# ltc3783-boost-driver-test-mk-1_0_0.net
KiCad netlist of a schematic drawn in EAGLE
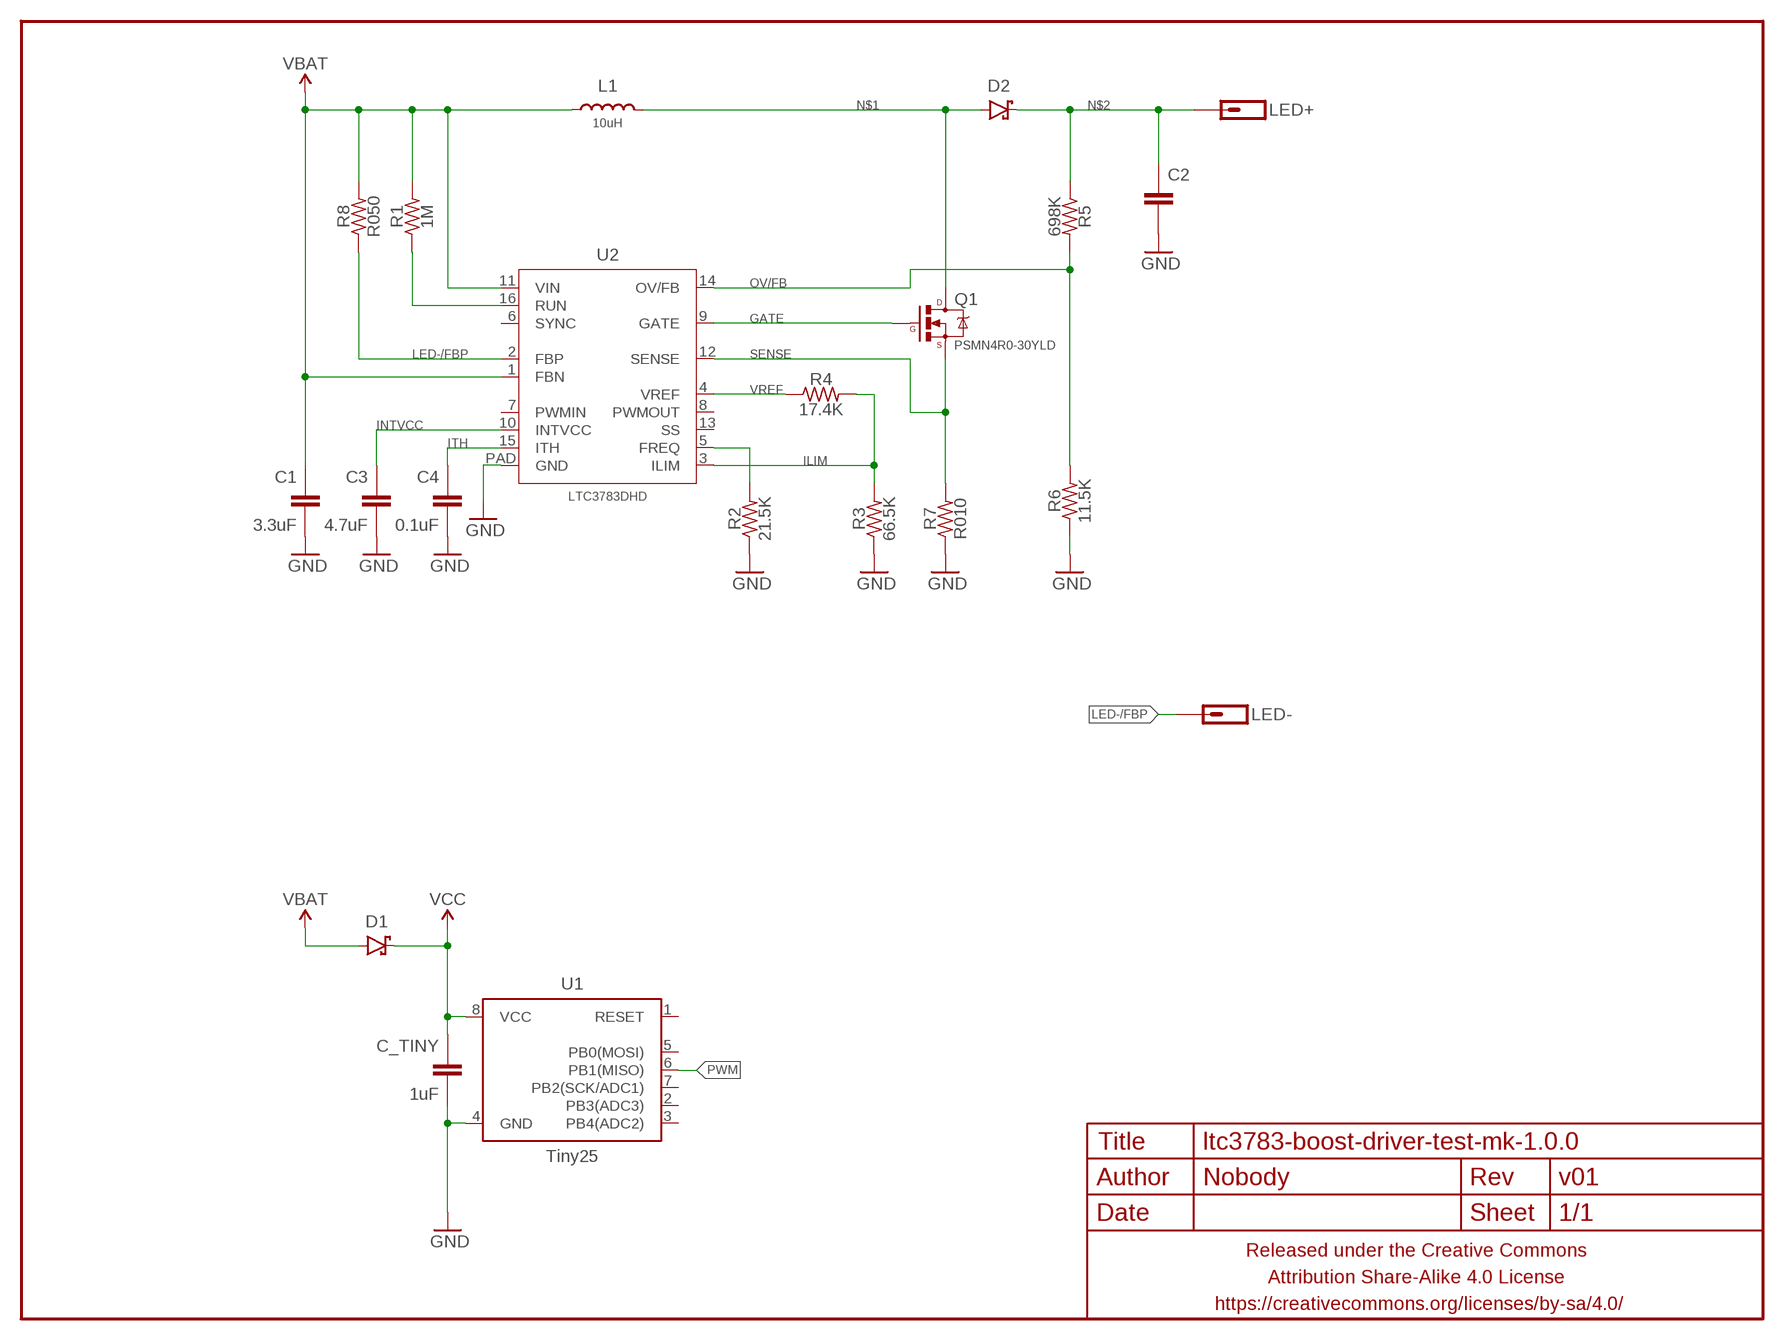
[diagram p0: schematic, sheet 1]

(export (version "E")
  (design (tool "Eeschema 10.0.6"))
  (components
    (comp (ref "C1")
      (value "3.3uF")
      (footprint "eagle-import:C0805-TIGHTER")
      (libsource (lib "eagle-import") (part "CAPACITOR-CERAMICC0805-TIGHTER"))
    )
    (comp (ref "C2")
      (value "CAPACITOR-CERAMICC0805-TIGHTER")
      (footprint "eagle-import:C0805-TIGHTER")
      (libsource (lib "eagle-import") (part "CAPACITOR-CERAMICC0805-TIGHTER"))
    )
    (comp (ref "C3")
      (value "4.7uF")
      (footprint "eagle-import:C0603-TIGHTER")
      (libsource (lib "eagle-import") (part "CAPACITOR-CERAMICC0603-TIGHTER"))
    )
    (comp (ref "C4")
      (value "0.1uF")
      (footprint "eagle-import:C0603-TIGHTER")
      (libsource (lib "eagle-import") (part "CAPACITOR-CERAMICC0603-TIGHTER"))
    )
    (comp (ref "C_TINY")
      (value "1uF")
      (footprint "eagle-import:C0402")
      (libsource (lib "eagle-import") (part "CAPACITOR-CERAMICC0402"))
    )
    (comp (ref "D1")
      (value "DIODE-SCHOTTKYSOD323")
      (footprint "eagle-import:SOD323-SCHOTTKY")
      (libsource (lib "eagle-import") (part "DIODE-SCHOTTKYSOD323"))
    )
    (comp (ref "D2")
      (value "DIODE-SCHOTTKYSOD323")
      (footprint "eagle-import:SOD323-SCHOTTKY")
      (libsource (lib "eagle-import") (part "DIODE-SCHOTTKYSOD323"))
    )
    (comp (ref "FRAME1")
      (value "FRAME-LETTERNO_PACKAGE")
      (footprint "eagle-import:DUMMY")
      (fields (field (name "DESIGNER") "Nobody"))
      (libsource (lib "eagle-import") (part "FRAME-LETTERNO_PACKAGE"))
    )
    (comp (ref "L1")
      (value "10uH")
      (footprint "eagle-import:XAL40X0")
      (libsource (lib "eagle-import") (part "INDUCTORXAL40X0"))
    )
    (comp (ref "LED+")
      (value "M01NOT-A-VIA-NOPE")
      (footprint "eagle-import:1X01_NOSILK_NOSTOP")
      (libsource (lib "eagle-import") (part "M01NOT-A-VIA-NOPE"))
    )
    (comp (ref "LED-")
      (value "M01NOT-A-VIA-NOPE")
      (footprint "eagle-import:1X01_NOSILK_NOSTOP")
      (libsource (lib "eagle-import") (part "M01NOT-A-VIA-NOPE"))
    )
    (comp (ref "Q1")
      (value "PSMN4R0-30YLD")
      (footprint "eagle-import:LFPAK33")
      (libsource (lib "eagle-import") (part "MOSFET-NCHANNELLFPAK33"))
    )
    (comp (ref "R1")
      (value "1M")
      (footprint "eagle-import:R0603-TIGHTER")
      (libsource (lib "eagle-import") (part "RESISTORR0603-TIGHTER"))
    )
    (comp (ref "R2")
      (value "21.5K")
      (footprint "eagle-import:R0603-TIGHTER")
      (libsource (lib "eagle-import") (part "RESISTORR0603-TIGHTER"))
    )
    (comp (ref "R3")
      (value "66.5K")
      (footprint "eagle-import:R0603-TIGHTER")
      (libsource (lib "eagle-import") (part "RESISTORR0603-TIGHTER"))
    )
    (comp (ref "R4")
      (value "17.4K")
      (footprint "eagle-import:R0603-TIGHTER")
      (libsource (lib "eagle-import") (part "RESISTORR0603-TIGHTER"))
    )
    (comp (ref "R5")
      (value "698K")
      (footprint "eagle-import:R0603-TIGHTER")
      (libsource (lib "eagle-import") (part "RESISTORR0603-TIGHTER"))
    )
    (comp (ref "R6")
      (value "11.5K")
      (footprint "eagle-import:R0603-TIGHTER")
      (libsource (lib "eagle-import") (part "RESISTORR0603-TIGHTER"))
    )
    (comp (ref "R7")
      (value "R010")
      (footprint "eagle-import:R0805-TIGHTER")
      (libsource (lib "eagle-import") (part "RESISTORR0805-TIGHTER"))
    )
    (comp (ref "R8")
      (value "R050")
      (footprint "eagle-import:R0805-TIGHTER")
      (libsource (lib "eagle-import") (part "RESISTORR0805-TIGHTER"))
    )
    (comp (ref "U1")
      (value "Tiny25")
      (footprint "eagle-import:SO08-SKINNYPADS")
      (libsource (lib "eagle-import") (part "ATTINY45TINY25-SOICN-NARROWER"))
    )
    (comp (ref "U2")
      (value "LTC3783DHD")
      (footprint "eagle-import:DFN400X400-16N")
      (libsource (lib "eagle-import") (part "LTC3783DHD"))
    )
  )
  (nets
    (net (code "1") (name "/GATE") (class "Default")
      (node (ref "Q1") (pin "4") (pinfunction "G_4") (pintype "passive"))
      (node (ref "U2") (pin "9") (pinfunction "GATE_9") (pintype "bidirectional"))
    )
    (net (code "2") (name "/ILIM") (class "Default")
      (node (ref "R3") (pin "2") (pinfunction "2_2") (pintype "passive"))
      (node (ref "R4") (pin "2") (pinfunction "2_2") (pintype "passive"))
      (node (ref "U2") (pin "3") (pinfunction "ILIM_3") (pintype "bidirectional"))
    )
    (net (code "3") (name "/INTVCC") (class "Default")
      (node (ref "C3") (pin "1") (pinfunction "1_1") (pintype "passive"))
      (node (ref "U2") (pin "10") (pinfunction "INTVCC_10") (pintype "bidirectional"))
    )
    (net (code "4") (name "/ITH") (class "Default")
      (node (ref "C4") (pin "1") (pinfunction "1_1") (pintype "passive"))
      (node (ref "U2") (pin "15") (pinfunction "ITH_15") (pintype "bidirectional"))
    )
    (net (code "5") (name "/N$1") (class "Default")
      (node (ref "D2") (pin "A") (pinfunction "A_A") (pintype "passive"))
      (node (ref "L1") (pin "P$2") (pinfunction "2_P$2") (pintype "passive"))
      (node (ref "Q1") (pin "PAD") (pinfunction "D_PAD") (pintype "passive"))
    )
    (net (code "6") (name "/N$2") (class "Default")
      (node (ref "C2") (pin "1") (pinfunction "1_1") (pintype "passive"))
      (node (ref "D2") (pin "C") (pinfunction "C_C") (pintype "passive"))
      (node (ref "LED+") (pin "P$1") (pinfunction "1_P$1") (pintype "passive"))
      (node (ref "R5") (pin "1") (pinfunction "1_1") (pintype "passive"))
    )
    (net (code "7") (name "/OV{slash}FB") (class "Default")
      (node (ref "R5") (pin "2") (pinfunction "2_2") (pintype "passive"))
      (node (ref "R6") (pin "2") (pinfunction "2_2") (pintype "passive"))
      (node (ref "U2") (pin "14") (pinfunction "OV/FB_14") (pintype "bidirectional"))
    )
    (net (code "8") (name "/SENSE") (class "Default")
      (node (ref "Q1") (pin "1") (pinfunction "S_1") (pintype "passive"))
      (node (ref "Q1") (pin "2") (pinfunction "S_2") (pintype "passive"))
      (node (ref "Q1") (pin "3") (pinfunction "S_3") (pintype "passive"))
      (node (ref "R7") (pin "2") (pinfunction "2_2") (pintype "passive"))
      (node (ref "U2") (pin "12") (pinfunction "SENSE_12") (pintype "bidirectional"))
    )
    (net (code "9") (name "/VREF") (class "Default")
      (node (ref "R4") (pin "1") (pinfunction "1_1") (pintype "passive"))
      (node (ref "U2") (pin "4") (pinfunction "VREF_4") (pintype "bidirectional"))
    )
    (net (code "10") (name "GND") (class "Default")
      (node (ref "C1") (pin "2") (pinfunction "2_2") (pintype "passive"))
      (node (ref "C2") (pin "2") (pinfunction "2_2") (pintype "passive"))
      (node (ref "C3") (pin "2") (pinfunction "2_2") (pintype "passive"))
      (node (ref "C4") (pin "2") (pinfunction "2_2") (pintype "passive"))
      (node (ref "C_TINY") (pin "2") (pinfunction "2_2") (pintype "passive"))
      (node (ref "R2") (pin "1") (pinfunction "1_1") (pintype "passive"))
      (node (ref "R3") (pin "1") (pinfunction "1_1") (pintype "passive"))
      (node (ref "R6") (pin "1") (pinfunction "1_1") (pintype "passive"))
      (node (ref "R7") (pin "1") (pinfunction "1_1") (pintype "passive"))
      (node (ref "U1") (pin "4") (pinfunction "GND_4") (pintype "bidirectional"))
      (node (ref "U2") (pin "PAD") (pinfunction "GND_PAD") (pintype "bidirectional"))
    )
    (net (code "11") (name "LED-{slash}FBP") (class "Default")
      (node (ref "LED-") (pin "P$1") (pinfunction "1_P$1") (pintype "passive"))
      (node (ref "R8") (pin "1") (pinfunction "1_1") (pintype "passive"))
      (node (ref "U2") (pin "2") (pinfunction "FBP_2") (pintype "bidirectional"))
    )
    (net (code "12") (name "Net-(U2-FREQ)") (class "Default")
      (node (ref "R2") (pin "2") (pinfunction "2_2") (pintype "passive"))
      (node (ref "U2") (pin "5") (pinfunction "FREQ_5") (pintype "bidirectional"))
    )
    (net (code "13") (name "Net-(U2-RUN)") (class "Default")
      (node (ref "R1") (pin "1") (pinfunction "1_1") (pintype "passive"))
      (node (ref "U2") (pin "16") (pinfunction "RUN_16") (pintype "bidirectional"))
    )
    (net (code "14") (name "PWM") (class "Default")
      (node (ref "U1") (pin "6") (pinfunction "PB1(MISO)_6") (pintype "bidirectional"))
    )
    (net (code "15") (name "VBAT") (class "Default")
      (node (ref "C1") (pin "1") (pinfunction "1_1") (pintype "passive"))
      (node (ref "D1") (pin "A") (pinfunction "A_A") (pintype "passive"))
      (node (ref "L1") (pin "P$1") (pinfunction "1_P$1") (pintype "passive"))
      (node (ref "R1") (pin "2") (pinfunction "2_2") (pintype "passive"))
      (node (ref "R8") (pin "2") (pinfunction "2_2") (pintype "passive"))
      (node (ref "U2") (pin "1") (pinfunction "FBN_1") (pintype "bidirectional"))
      (node (ref "U2") (pin "11") (pinfunction "VIN_11") (pintype "bidirectional"))
    )
    (net (code "16") (name "VCC") (class "Default")
      (node (ref "C_TINY") (pin "1") (pinfunction "1_1") (pintype "passive"))
      (node (ref "D1") (pin "C") (pinfunction "C_C") (pintype "passive"))
      (node (ref "U1") (pin "8") (pinfunction "VCC_8") (pintype "bidirectional"))
    )
    (net (code "17") (name "unconnected-(U1-PB0(MOSI)-Pad5)") (class "Default")
      (node (ref "U1") (pin "5") (pinfunction "PB0(MOSI)_5") (pintype "bidirectional"))
    )
    (net (code "18") (name "unconnected-(U1-PB2(SCK{slash}ADC1)-Pad7)") (class "Default")
      (node (ref "U1") (pin "7") (pinfunction "PB2(SCK/ADC1)_7") (pintype "bidirectional"))
    )
    (net (code "19") (name "unconnected-(U1-PB3(ADC3)-Pad2)") (class "Default")
      (node (ref "U1") (pin "2") (pinfunction "PB3(ADC3)_2") (pintype "bidirectional"))
    )
    (net (code "20") (name "unconnected-(U1-PB4(ADC2)-Pad3)") (class "Default")
      (node (ref "U1") (pin "3") (pinfunction "PB4(ADC2)_3") (pintype "bidirectional"))
    )
    (net (code "21") (name "unconnected-(U1-RESET-Pad1)") (class "Default")
      (node (ref "U1") (pin "1") (pinfunction "RESET_1") (pintype "bidirectional"))
    )
    (net (code "22") (name "unconnected-(U2-PWMIN-Pad7)") (class "Default")
      (node (ref "U2") (pin "7") (pinfunction "PWMIN_7") (pintype "bidirectional"))
    )
    (net (code "23") (name "unconnected-(U2-PWMOUT-Pad8)") (class "Default")
      (node (ref "U2") (pin "8") (pinfunction "PWMOUT_8") (pintype "bidirectional"))
    )
    (net (code "24") (name "unconnected-(U2-SS-Pad13)") (class "Default")
      (node (ref "U2") (pin "13") (pinfunction "SS_13") (pintype "bidirectional"))
    )
    (net (code "25") (name "unconnected-(U2-SYNC-Pad6)") (class "Default")
      (node (ref "U2") (pin "6") (pinfunction "SYNC_6") (pintype "bidirectional"))
    )
  )
)
